# esp8266_1D_noGND.net
KiCad netlist of a schematic drawn in EAGLE
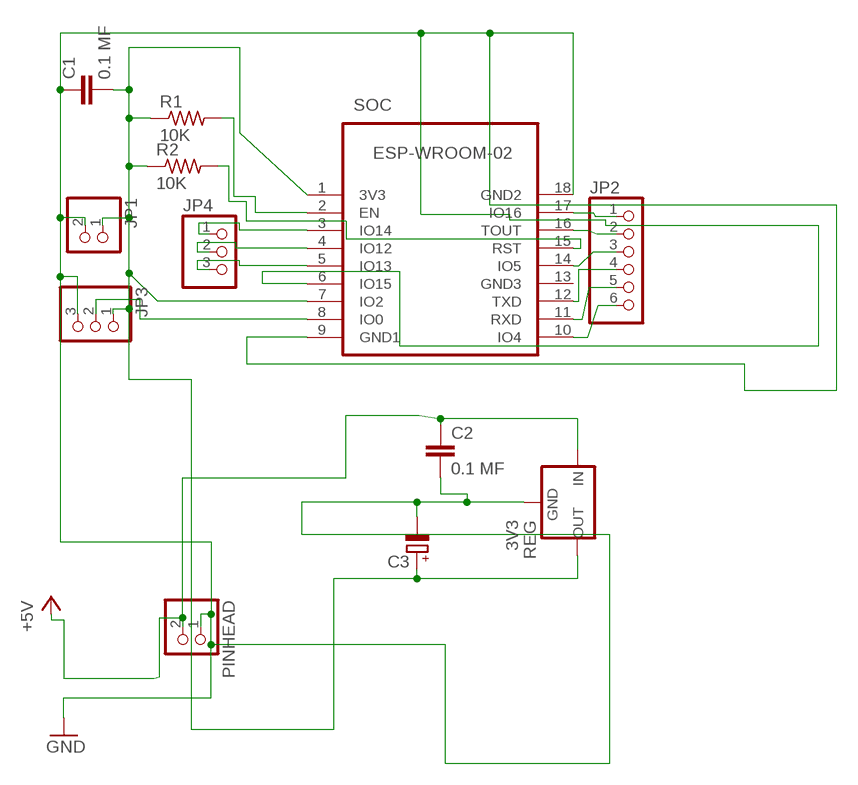
[diagram p0: schematic, sheet 1]

(export (version "E")
  (design (tool "Eeschema 10.0.6"))
  (components
    (comp (ref "C1")
      (value "0.1 MF")
      (footprint "eagle-import:C025-024X044")
      (libsource (lib "eagle-import") (part "C-EU025-024X044"))
    )
    (comp (ref "C2")
      (value "0.1 MF")
      (footprint "eagle-import:C025-024X044")
      (libsource (lib "eagle-import") (part "C-EU025-024X044"))
    )
    (comp (ref "C3")
      (value "CPOL-EUE2.5-7")
      (footprint "eagle-import:E2,5-7")
      (libsource (lib "eagle-import") (part "CPOL-EUE2.5-7"))
    )
    (comp (ref "JP1")
      (value "PINHD-1X2")
      (footprint "eagle-import:1X02")
      (libsource (lib "eagle-import") (part "PINHD-1X2"))
    )
    (comp (ref "JP2")
      (value "PINHD-1X6")
      (footprint "eagle-import:1X06")
      (libsource (lib "eagle-import") (part "PINHD-1X6"))
    )
    (comp (ref "JP3")
      (value "PINHD-1X3")
      (footprint "eagle-import:1X03")
      (libsource (lib "eagle-import") (part "PINHD-1X3"))
    )
    (comp (ref "JP4")
      (value "PINHD-1X3")
      (footprint "eagle-import:1X03")
      (libsource (lib "eagle-import") (part "PINHD-1X3"))
    )
    (comp (ref "PINHEAD")
      (value "PINHD-1X2")
      (footprint "eagle-import:1X02")
      (libsource (lib "eagle-import") (part "PINHD-1X2"))
    )
    (comp (ref "R1")
      (value "10K")
      (footprint "eagle-import:0204_7")
      (libsource (lib "eagle-import") (part "R-US_0204/7"))
    )
    (comp (ref "R2")
      (value "10K")
      (footprint "eagle-import:0204_7")
      (libsource (lib "eagle-import") (part "R-US_0204/7"))
    )
    (comp (ref "REG")
      (value "3V3")
      (footprint "eagle-import:78XXS")
      (libsource (lib "eagle-import") (part "78XXS"))
    )
    (comp (ref "SOC")
      (value "ESP-WROOM-02")
      (footprint "eagle-import:FRONT-FACE-CP2")
      (libsource (lib "eagle-import") (part "ESP-WROOM-02-CP2FRONT"))
    )
  )
  (nets
    (net (code "1") (name "+5V") (class "Default")
      (node (ref "C2") (pin "1") (pinfunction "1_1") (pintype "passive"))
      (node (ref "PINHEAD") (pin "2") (pinfunction "2_2") (pintype "passive"))
      (node (ref "REG") (pin "IN") (pinfunction "IN_IN") (pintype "input"))
    )
    (net (code "2") (name "GND") (class "Default")
      (node (ref "C1") (pin "1") (pinfunction "1_1") (pintype "passive"))
      (node (ref "C2") (pin "2") (pinfunction "2_2") (pintype "passive"))
      (node (ref "C3") (pin "-") (pinfunction "-_-") (pintype "passive"))
      (node (ref "JP1") (pin "2") (pinfunction "2_2") (pintype "passive"))
      (node (ref "JP3") (pin "3") (pinfunction "3_3") (pintype "passive"))
      (node (ref "PINHEAD") (pin "1") (pinfunction "1_1") (pintype "passive"))
      (node (ref "REG") (pin "GND") (pinfunction "GND_GND") (pintype "input"))
      (node (ref "SOC") (pin "18") (pinfunction "GND2_18") (pintype "bidirectional"))
      (node (ref "SOC") (pin "6") (pinfunction "IO15_6") (pintype "bidirectional"))
      (node (ref "SOC") (pin "9") (pinfunction "GND1_9") (pintype "bidirectional"))
    )
    (net (code "3") (name "Net-(SOC-3V3)") (class "Default")
      (node (ref "C1") (pin "2") (pinfunction "2_2") (pintype "passive"))
      (node (ref "C3") (pin "+") (pinfunction "+_+") (pintype "passive"))
      (node (ref "JP1") (pin "1") (pinfunction "1_1") (pintype "passive"))
      (node (ref "JP3") (pin "1") (pinfunction "1_1") (pintype "passive"))
      (node (ref "R1") (pin "1") (pinfunction "1_1") (pintype "passive"))
      (node (ref "R2") (pin "1") (pinfunction "1_1") (pintype "passive"))
      (node (ref "REG") (pin "OUT") (pinfunction "OUT_OUT") (pintype "passive"))
      (node (ref "SOC") (pin "1") (pinfunction "3V3_1") (pintype "bidirectional"))
      (node (ref "SOC") (pin "7") (pinfunction "IO2_7") (pintype "bidirectional"))
    )
    (net (code "4") (name "Net-(SOC-EN)") (class "Default")
      (node (ref "R1") (pin "2") (pinfunction "2_2") (pintype "passive"))
      (node (ref "SOC") (pin "2") (pinfunction "EN_2") (pintype "bidirectional"))
    )
    (net (code "5") (name "Net-(SOC-IO0)") (class "Default")
      (node (ref "JP3") (pin "2") (pinfunction "2_2") (pintype "passive"))
      (node (ref "SOC") (pin "8") (pinfunction "IO0_8") (pintype "bidirectional"))
    )
    (net (code "6") (name "Net-(SOC-IO4)") (class "Default")
      (node (ref "JP2") (pin "6") (pinfunction "6_6") (pintype "passive"))
      (node (ref "SOC") (pin "10") (pinfunction "IO4_10") (pintype "bidirectional"))
    )
    (net (code "7") (name "Net-(SOC-IO5)") (class "Default")
      (node (ref "JP2") (pin "3") (pinfunction "3_3") (pintype "passive"))
      (node (ref "SOC") (pin "14") (pinfunction "IO5_14") (pintype "bidirectional"))
    )
    (net (code "8") (name "Net-(SOC-IO12)") (class "Default")
      (node (ref "JP4") (pin "2") (pinfunction "2_2") (pintype "passive"))
      (node (ref "SOC") (pin "4") (pinfunction "IO12_4") (pintype "bidirectional"))
    )
    (net (code "9") (name "Net-(SOC-IO13)") (class "Default")
      (node (ref "JP4") (pin "3") (pinfunction "3_3") (pintype "passive"))
      (node (ref "SOC") (pin "5") (pinfunction "IO13_5") (pintype "open_collector"))
    )
    (net (code "10") (name "Net-(SOC-IO14)") (class "Default")
      (node (ref "JP4") (pin "1") (pinfunction "1_1") (pintype "passive"))
      (node (ref "SOC") (pin "3") (pinfunction "IO14_3") (pintype "bidirectional"))
    )
    (net (code "11") (name "Net-(SOC-IO16)") (class "Default")
      (node (ref "JP2") (pin "1") (pinfunction "1_1") (pintype "passive"))
      (node (ref "SOC") (pin "17") (pinfunction "IO16_17") (pintype "bidirectional"))
    )
    (net (code "12") (name "Net-(SOC-RST)") (class "Default")
      (node (ref "R2") (pin "2") (pinfunction "2_2") (pintype "passive"))
      (node (ref "SOC") (pin "15") (pinfunction "RST_15") (pintype "bidirectional"))
    )
    (net (code "13") (name "Net-(SOC-RXD)") (class "Default")
      (node (ref "JP2") (pin "5") (pinfunction "5_5") (pintype "passive"))
      (node (ref "SOC") (pin "11") (pinfunction "RXD_11") (pintype "bidirectional"))
    )
    (net (code "14") (name "Net-(SOC-TOUT)") (class "Default")
      (node (ref "JP2") (pin "2") (pinfunction "2_2") (pintype "passive"))
      (node (ref "SOC") (pin "16") (pinfunction "TOUT_16") (pintype "bidirectional"))
    )
    (net (code "15") (name "Net-(SOC-TXD)") (class "Default")
      (node (ref "JP2") (pin "4") (pinfunction "4_4") (pintype "passive"))
      (node (ref "SOC") (pin "12") (pinfunction "TXD_12") (pintype "bidirectional"))
    )
    (net (code "16") (name "unconnected-(SOC-GND3-Pad13)") (class "Default")
      (node (ref "SOC") (pin "13") (pinfunction "GND3_13") (pintype "bidirectional"))
    )
  )
)
